# ISO485.net
KiCad netlist of a schematic drawn in EAGLE
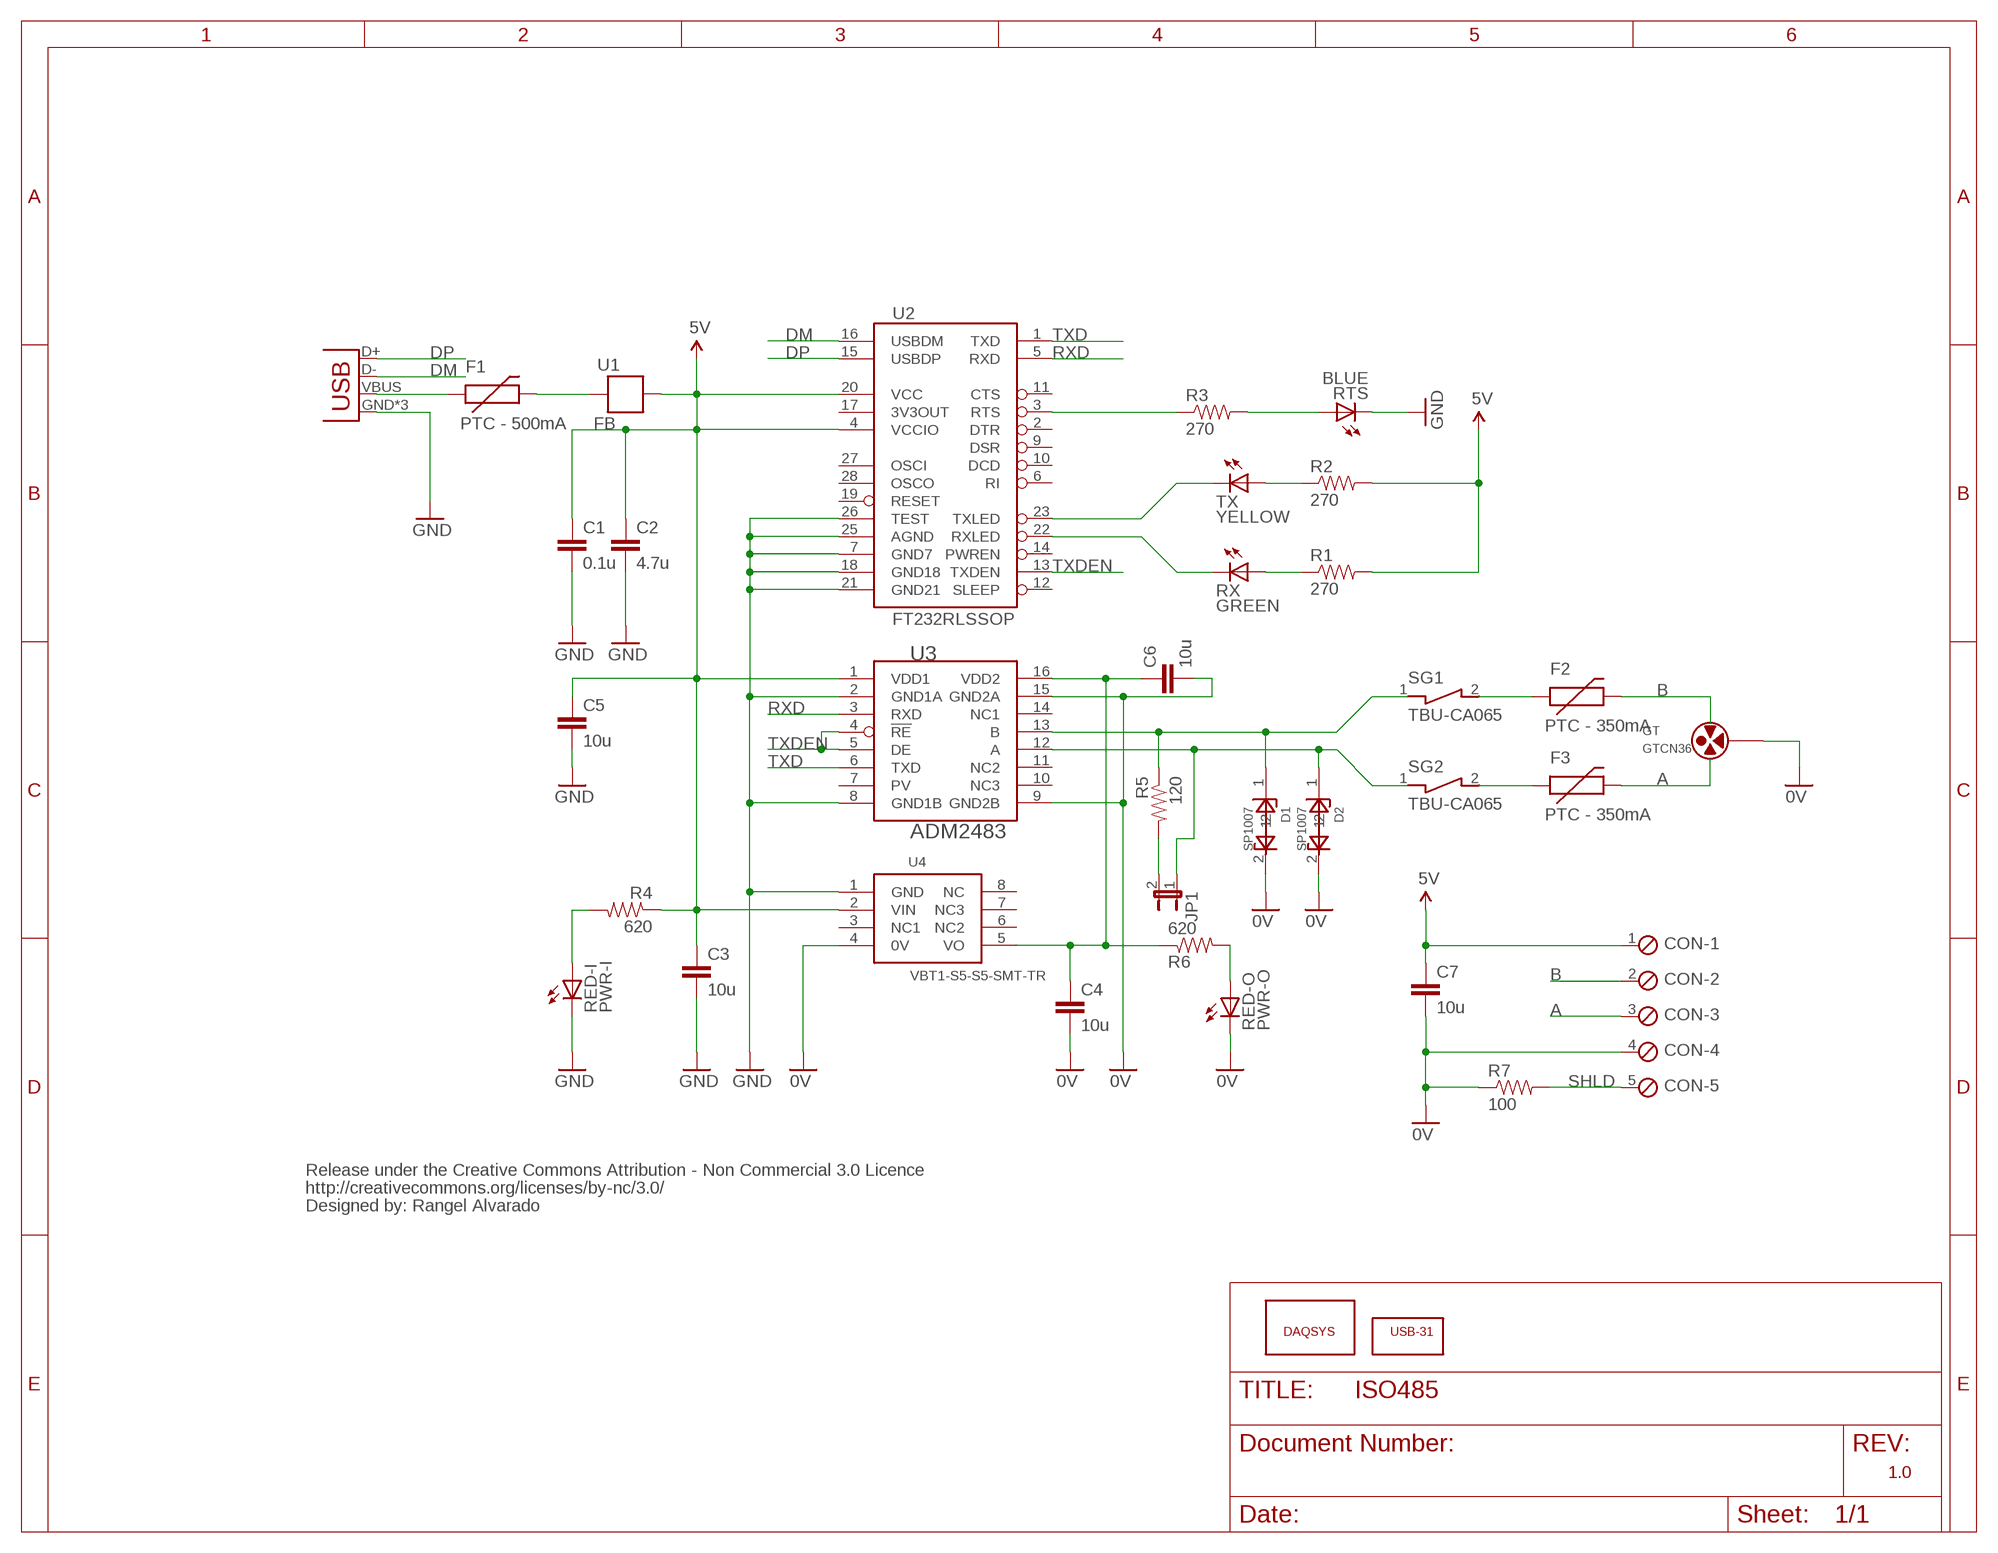
[diagram p0: schematic, sheet 1]

(export (version "E")
  (design (tool "Eeschema 10.0.6"))
  (components
    (comp (ref "C1")
      (value "0.1u")
      (footprint "eagle-import:0603-CAP")
      (libsource (lib "eagle-import") (part "CAP0603-CAP"))
    )
    (comp (ref "C2")
      (value "4.7u")
      (footprint "eagle-import:0603-CAP")
      (libsource (lib "eagle-import") (part "CAP0603-CAP"))
    )
    (comp (ref "C3")
      (value "10u")
      (footprint "eagle-import:0603-CAP")
      (libsource (lib "eagle-import") (part "CAP0603-CAP"))
    )
    (comp (ref "C4")
      (value "10u")
      (footprint "eagle-import:0603-CAP")
      (libsource (lib "eagle-import") (part "CAP0603-CAP"))
    )
    (comp (ref "C5")
      (value "10u")
      (footprint "eagle-import:0603-CAP")
      (libsource (lib "eagle-import") (part "CAP0603-CAP"))
    )
    (comp (ref "C6")
      (value "10u")
      (footprint "eagle-import:0603-CAP")
      (libsource (lib "eagle-import") (part "CAP0603-CAP"))
    )
    (comp (ref "C7")
      (value "10u")
      (footprint "eagle-import:0603-CAP")
      (libsource (lib "eagle-import") (part "CAP0603-CAP"))
    )
    (comp (ref "CON")
      (value "MPT5")
      (footprint "eagle-import:5POL254")
      (libsource (lib "eagle-import") (part "MPT5"))
    )
    (comp (ref "D1")
      (value "SP1007")
      (footprint "eagle-import:0603")
      (libsource (lib "eagle-import") (part "SP1007-01WTG"))
    )
    (comp (ref "D2")
      (value "SP1007")
      (footprint "eagle-import:0603")
      (libsource (lib "eagle-import") (part "SP1007-01WTG"))
    )
    (comp (ref "F1")
      (value "PTC - 500mA")
      (footprint "eagle-import:0603")
      (libsource (lib "eagle-import") (part "PTC0603"))
    )
    (comp (ref "F2")
      (value "PTC - 350mA")
      (footprint "eagle-import:0603")
      (libsource (lib "eagle-import") (part "PTC0603"))
    )
    (comp (ref "F3")
      (value "PTC - 350mA")
      (footprint "eagle-import:0603")
      (libsource (lib "eagle-import") (part "PTC0603"))
    )
    (comp (ref "GT")
      (value "GTCN36")
      (footprint "eagle-import:SMT-GDT")
      (libsource (lib "eagle-import") (part "GTCN36-401M-R05"))
    )
    (comp (ref "JP1")
      (value "JUMPER-2PTH")
      (footprint "eagle-import:1X02")
      (libsource (lib "eagle-import") (part "JUMPER-2PTH"))
    )
    (comp (ref "R1")
      (value "270")
      (footprint "eagle-import:0402-RES")
      (libsource (lib "eagle-import") (part "RESISTOR0402-RES"))
    )
    (comp (ref "R2")
      (value "270")
      (footprint "eagle-import:0402-RES")
      (libsource (lib "eagle-import") (part "RESISTOR0402-RES"))
    )
    (comp (ref "R3")
      (value "270")
      (footprint "eagle-import:0402-RES")
      (libsource (lib "eagle-import") (part "RESISTOR0402-RES"))
    )
    (comp (ref "R4")
      (value "620")
      (footprint "eagle-import:0402-RES")
      (libsource (lib "eagle-import") (part "RESISTOR0402-RES"))
    )
    (comp (ref "R5")
      (value "120")
      (footprint "eagle-import:0402-RES")
      (libsource (lib "eagle-import") (part "RESISTOR0402-RES"))
    )
    (comp (ref "R6")
      (value "620")
      (footprint "eagle-import:0402-RES")
      (libsource (lib "eagle-import") (part "RESISTOR0402-RES"))
    )
    (comp (ref "R7")
      (value "100")
      (footprint "eagle-import:1206")
      (libsource (lib "eagle-import") (part "RESISTOR1206"))
    )
    (comp (ref "RED-I")
      (value "PWR-I")
      (footprint "eagle-import:LED-1206")
      (libsource (lib "eagle-import") (part "LED1206"))
    )
    (comp (ref "RED-O")
      (value "PWR-O")
      (footprint "eagle-import:LED-1206")
      (libsource (lib "eagle-import") (part "LED1206"))
    )
    (comp (ref "RTS")
      (value "BLUE")
      (footprint "eagle-import:LED-0603")
      (libsource (lib "eagle-import") (part "LED0603"))
    )
    (comp (ref "RX")
      (value "GREEN")
      (footprint "eagle-import:LED-0603")
      (libsource (lib "eagle-import") (part "LED-GREEN0603"))
    )
    (comp (ref "SG1")
      (value "TBU-CA065")
      (footprint "eagle-import:SMD")
      (libsource (lib "eagle-import") (part "TBU-CA065-100-WH"))
    )
    (comp (ref "SG2")
      (value "TBU-CA065")
      (footprint "eagle-import:SMD")
      (libsource (lib "eagle-import") (part "TBU-CA065-100-WH"))
    )
    (comp (ref "TX")
      (value "YELLOW")
      (footprint "eagle-import:LED-0603")
      (libsource (lib "eagle-import") (part "LED-YELLOW0603"))
    )
    (comp (ref "U$1")
      (value "CC-BY-NC")
      (footprint "eagle-import:CC-BY-NC")
      (libsource (lib "eagle-import") (part "CC-BY-NC"))
    )
    (comp (ref "U$2")
      (value "DAQSYS")
      (footprint "eagle-import:DAQSYS")
      (libsource (lib "eagle-import") (part "DAQSYS"))
    )
    (comp (ref "U$3")
      (value "USB-31")
      (footprint "eagle-import:USB-PCB-RECT")
      (libsource (lib "eagle-import") (part "USB-31"))
    )
    (comp (ref "U1")
      (value "FB")
      (footprint "eagle-import:0603")
      (libsource (lib "eagle-import") (part "FB"))
    )
    (comp (ref "U2")
      (value "FT232RLSSOP")
      (footprint "eagle-import:SSOP28DB")
      (libsource (lib "eagle-import") (part "FT232RLSSOP"))
    )
    (comp (ref "U3")
      (value "ADM2483")
      (footprint "eagle-import:SOIC-16")
      (libsource (lib "eagle-import") (part "ADM2483"))
    )
    (comp (ref "U4")
      (value "VBT1-S5-S5-SMT-TR")
      (footprint "eagle-import:SMD-8")
      (libsource (lib "eagle-import") (part "VBT1-S5-S5-SMT-TR"))
    )
    (comp (ref "USB")
      (value "USB-MICROB")
      (footprint "eagle-import:USB-MICROB")
      (libsource (lib "eagle-import") (part "USB-MICROB"))
    )
  )
  (nets
    (net (code "1") (name "/A") (class "Default")
      (node (ref "CON") (pin "3") (pinfunction "1_3") (pintype "passive"))
      (node (ref "F3") (pin "2") (pinfunction "2_2") (pintype "bidirectional"))
      (node (ref "GT") (pin "2") (pinfunction "2_2") (pintype "bidirectional"))
    )
    (net (code "2") (name "/B") (class "Default")
      (node (ref "CON") (pin "2") (pinfunction "1_2") (pintype "passive"))
      (node (ref "F2") (pin "2") (pinfunction "2_2") (pintype "bidirectional"))
      (node (ref "GT") (pin "1") (pinfunction "1_1") (pintype "bidirectional"))
    )
    (net (code "3") (name "/DM") (class "Default")
      (node (ref "U2") (pin "16") (pinfunction "USBDM_16") (pintype "bidirectional"))
      (node (ref "USB") (pin "D-") (pinfunction "D-_D-") (pintype "bidirectional"))
    )
    (net (code "4") (name "/DP") (class "Default")
      (node (ref "U2") (pin "15") (pinfunction "USBDP_15") (pintype "bidirectional"))
      (node (ref "USB") (pin "D+") (pinfunction "D+_D+") (pintype "bidirectional"))
    )
    (net (code "5") (name "/RXD") (class "Default")
      (node (ref "U2") (pin "5") (pinfunction "RXD_5") (pintype "input"))
      (node (ref "U3") (pin "3") (pinfunction "RXD_3") (pintype "bidirectional"))
    )
    (net (code "6") (name "/SHLD") (class "Default")
      (node (ref "CON") (pin "5") (pinfunction "1_5") (pintype "passive"))
      (node (ref "R7") (pin "2") (pinfunction "2_2") (pintype "passive"))
    )
    (net (code "7") (name "/TXD") (class "Default")
      (node (ref "U2") (pin "1") (pinfunction "TXD_1") (pintype "output"))
      (node (ref "U3") (pin "6") (pinfunction "TXD_6") (pintype "bidirectional"))
    )
    (net (code "8") (name "/TXDEN") (class "Default")
      (node (ref "U2") (pin "13") (pinfunction "TXDEN_13") (pintype "input"))
      (node (ref "U3") (pin "4") (pinfunction "~{RE}_4") (pintype "bidirectional"))
      (node (ref "U3") (pin "5") (pinfunction "DE_5") (pintype "bidirectional"))
    )
    (net (code "9") (name "0V") (class "Default")
      (node (ref "C4") (pin "2") (pinfunction "2_2") (pintype "passive"))
      (node (ref "C6") (pin "2") (pinfunction "2_2") (pintype "passive"))
      (node (ref "C7") (pin "2") (pinfunction "2_2") (pintype "passive"))
      (node (ref "CON") (pin "4") (pinfunction "1_4") (pintype "passive"))
      (node (ref "D1") (pin "2") (pinfunction "2_2") (pintype "bidirectional"))
      (node (ref "D2") (pin "2") (pinfunction "2_2") (pintype "bidirectional"))
      (node (ref "GT") (pin "3") (pinfunction "3_3") (pintype "bidirectional"))
      (node (ref "R7") (pin "1") (pinfunction "1_1") (pintype "passive"))
      (node (ref "RED-O") (pin "C") (pinfunction "C_C") (pintype "passive"))
      (node (ref "U3") (pin "15") (pinfunction "GND2A_15") (pintype "bidirectional"))
      (node (ref "U3") (pin "9") (pinfunction "GND2B_9") (pintype "bidirectional"))
      (node (ref "U4") (pin "4") (pinfunction "0V_4") (pintype "bidirectional"))
    )
    (net (code "10") (name "5V") (class "Default")
      (node (ref "C1") (pin "1") (pinfunction "1_1") (pintype "passive"))
      (node (ref "C2") (pin "1") (pinfunction "1_1") (pintype "passive"))
      (node (ref "C3") (pin "1") (pinfunction "1_1") (pintype "passive"))
      (node (ref "C5") (pin "1") (pinfunction "1_1") (pintype "passive"))
      (node (ref "C7") (pin "1") (pinfunction "1_1") (pintype "passive"))
      (node (ref "CON") (pin "1") (pinfunction "1_1") (pintype "passive"))
      (node (ref "R1") (pin "2") (pinfunction "2_2") (pintype "passive"))
      (node (ref "R2") (pin "2") (pinfunction "2_2") (pintype "passive"))
      (node (ref "R4") (pin "1") (pinfunction "1_1") (pintype "passive"))
      (node (ref "U1") (pin "1") (pinfunction "P$1_1") (pintype "bidirectional"))
      (node (ref "U2") (pin "20") (pinfunction "VCC_20") (pintype "power_in"))
      (node (ref "U2") (pin "4") (pinfunction "VCCIO_4") (pintype "power_in"))
      (node (ref "U3") (pin "1") (pinfunction "VDD1_1") (pintype "bidirectional"))
      (node (ref "U4") (pin "2") (pinfunction "VIN_2") (pintype "bidirectional"))
    )
    (net (code "11") (name "GND") (class "Default")
      (node (ref "C1") (pin "2") (pinfunction "2_2") (pintype "passive"))
      (node (ref "C2") (pin "2") (pinfunction "2_2") (pintype "passive"))
      (node (ref "C3") (pin "2") (pinfunction "2_2") (pintype "passive"))
      (node (ref "C5") (pin "2") (pinfunction "2_2") (pintype "passive"))
      (node (ref "RED-I") (pin "C") (pinfunction "C_C") (pintype "passive"))
      (node (ref "RTS") (pin "C") (pinfunction "C_C") (pintype "passive"))
      (node (ref "U2") (pin "18") (pinfunction "GND18_18") (pintype "power_in"))
      (node (ref "U2") (pin "21") (pinfunction "GND21_21") (pintype "power_in"))
      (node (ref "U2") (pin "25") (pinfunction "AGND_25") (pintype "power_in"))
      (node (ref "U2") (pin "26") (pinfunction "TEST_26") (pintype "input"))
      (node (ref "U2") (pin "7") (pinfunction "GND7_7") (pintype "power_in"))
      (node (ref "U3") (pin "2") (pinfunction "GND1A_2") (pintype "bidirectional"))
      (node (ref "U3") (pin "8") (pinfunction "GND1B_8") (pintype "bidirectional"))
      (node (ref "U4") (pin "1") (pinfunction "GND_1") (pintype "bidirectional"))
      (node (ref "USB") (pin "GND") (pinfunction "GND_GND") (pintype "bidirectional"))
      (node (ref "USB") (pin "MT1") (pinfunction "GND_MT1") (pintype "bidirectional"))
      (node (ref "USB") (pin "MT2") (pinfunction "GND_MT2") (pintype "bidirectional"))
    )
    (net (code "12") (name "Net-(F1-Pad1)") (class "Default")
      (node (ref "F1") (pin "1") (pinfunction "1_1") (pintype "bidirectional"))
      (node (ref "USB") (pin "VBUS") (pinfunction "VBUS_VBUS") (pintype "bidirectional"))
    )
    (net (code "13") (name "Net-(JP1-Pad2)") (class "Default")
      (node (ref "JP1") (pin "2") (pinfunction "2_2") (pintype "passive"))
      (node (ref "R5") (pin "2") (pinfunction "2_2") (pintype "passive"))
    )
    (net (code "14") (name "Net-(R1-Pad1)") (class "Default")
      (node (ref "R1") (pin "1") (pinfunction "1_1") (pintype "passive"))
      (node (ref "RX") (pin "A") (pinfunction "A_A") (pintype "passive"))
    )
    (net (code "15") (name "Net-(R2-Pad1)") (class "Default")
      (node (ref "R2") (pin "1") (pinfunction "1_1") (pintype "passive"))
      (node (ref "TX") (pin "A") (pinfunction "A_A") (pintype "passive"))
    )
    (net (code "16") (name "Net-(R3-Pad2)") (class "Default")
      (node (ref "R3") (pin "2") (pinfunction "2_2") (pintype "passive"))
      (node (ref "RTS") (pin "A") (pinfunction "A_A") (pintype "passive"))
    )
    (net (code "17") (name "Net-(R4-Pad2)") (class "Default")
      (node (ref "R4") (pin "2") (pinfunction "2_2") (pintype "passive"))
      (node (ref "RED-I") (pin "A") (pinfunction "A_A") (pintype "passive"))
    )
    (net (code "18") (name "Net-(R6-Pad2)") (class "Default")
      (node (ref "R6") (pin "2") (pinfunction "2_2") (pintype "passive"))
      (node (ref "RED-O") (pin "A") (pinfunction "A_A") (pintype "passive"))
    )
    (net (code "19") (name "Net-(SG1-P$1)") (class "Default")
      (node (ref "D1") (pin "1") (pinfunction "1_1") (pintype "bidirectional"))
      (node (ref "R5") (pin "1") (pinfunction "1_1") (pintype "passive"))
      (node (ref "SG1") (pin "1") (pinfunction "P$1_1") (pintype "bidirectional"))
      (node (ref "U3") (pin "13") (pinfunction "B_13") (pintype "bidirectional"))
    )
    (net (code "20") (name "Net-(SG1-P$2)") (class "Default")
      (node (ref "F2") (pin "1") (pinfunction "1_1") (pintype "bidirectional"))
      (node (ref "SG1") (pin "2") (pinfunction "P$2_2") (pintype "bidirectional"))
    )
    (net (code "21") (name "Net-(SG2-P$1)") (class "Default")
      (node (ref "D2") (pin "1") (pinfunction "1_1") (pintype "bidirectional"))
      (node (ref "JP1") (pin "1") (pinfunction "1_1") (pintype "passive"))
      (node (ref "SG2") (pin "1") (pinfunction "P$1_1") (pintype "bidirectional"))
      (node (ref "U3") (pin "12") (pinfunction "A_12") (pintype "bidirectional"))
    )
    (net (code "22") (name "Net-(SG2-P$2)") (class "Default")
      (node (ref "F3") (pin "1") (pinfunction "1_1") (pintype "bidirectional"))
      (node (ref "SG2") (pin "2") (pinfunction "P$2_2") (pintype "bidirectional"))
    )
    (net (code "23") (name "Net-(U1-P$2)") (class "Default")
      (node (ref "F1") (pin "2") (pinfunction "2_2") (pintype "bidirectional"))
      (node (ref "U1") (pin "2") (pinfunction "P$2_2") (pintype "bidirectional"))
    )
    (net (code "24") (name "Net-(U2-RTS)") (class "Default")
      (node (ref "R3") (pin "1") (pinfunction "1_1") (pintype "passive"))
      (node (ref "U2") (pin "3") (pinfunction "RTS_3") (pintype "output"))
    )
    (net (code "25") (name "Net-(U2-RXLED)") (class "Default")
      (node (ref "RX") (pin "C") (pinfunction "C_C") (pintype "passive"))
      (node (ref "U2") (pin "22") (pinfunction "RXLED_22") (pintype "input"))
    )
    (net (code "26") (name "Net-(U2-TXLED)") (class "Default")
      (node (ref "TX") (pin "C") (pinfunction "C_C") (pintype "passive"))
      (node (ref "U2") (pin "23") (pinfunction "TXLED_23") (pintype "input"))
    )
    (net (code "27") (name "Net-(U3-VDD2)") (class "Default")
      (node (ref "C4") (pin "1") (pinfunction "1_1") (pintype "passive"))
      (node (ref "C6") (pin "1") (pinfunction "1_1") (pintype "passive"))
      (node (ref "R6") (pin "1") (pinfunction "1_1") (pintype "passive"))
      (node (ref "U3") (pin "16") (pinfunction "VDD2_16") (pintype "bidirectional"))
      (node (ref "U4") (pin "5") (pinfunction "VO_5") (pintype "bidirectional"))
    )
    (net (code "28") (name "unconnected-(U2-3V3OUT-Pad17)") (class "Default")
      (node (ref "U2") (pin "17") (pinfunction "3V3OUT_17") (pintype "output"))
    )
    (net (code "29") (name "unconnected-(U2-CTS-Pad11)") (class "Default")
      (node (ref "U2") (pin "11") (pinfunction "CTS_11") (pintype "input"))
    )
    (net (code "30") (name "unconnected-(U2-DCD-Pad10)") (class "Default")
      (node (ref "U2") (pin "10") (pinfunction "DCD_10") (pintype "input"))
    )
    (net (code "31") (name "unconnected-(U2-DSR-Pad9)") (class "Default")
      (node (ref "U2") (pin "9") (pinfunction "DSR_9") (pintype "input"))
    )
    (net (code "32") (name "unconnected-(U2-DTR-Pad2)") (class "Default")
      (node (ref "U2") (pin "2") (pinfunction "DTR_2") (pintype "output"))
    )
    (net (code "33") (name "unconnected-(U2-OSCI-Pad27)") (class "Default")
      (node (ref "U2") (pin "27") (pinfunction "OSCI_27") (pintype "input"))
    )
    (net (code "34") (name "unconnected-(U2-OSCO-Pad28)") (class "Default")
      (node (ref "U2") (pin "28") (pinfunction "OSCO_28") (pintype "output"))
    )
    (net (code "35") (name "unconnected-(U2-PWREN-Pad14)") (class "Default")
      (node (ref "U2") (pin "14") (pinfunction "PWREN_14") (pintype "input"))
    )
    (net (code "36") (name "unconnected-(U2-RESET-Pad19)") (class "Default")
      (node (ref "U2") (pin "19") (pinfunction "RESET_19") (pintype "input"))
    )
    (net (code "37") (name "unconnected-(U2-RI-Pad6)") (class "Default")
      (node (ref "U2") (pin "6") (pinfunction "RI_6") (pintype "input"))
    )
    (net (code "38") (name "unconnected-(U2-SLEEP-Pad12)") (class "Default")
      (node (ref "U2") (pin "12") (pinfunction "SLEEP_12") (pintype "input"))
    )
    (net (code "39") (name "unconnected-(U3-NC1-Pad14)") (class "Default")
      (node (ref "U3") (pin "14") (pinfunction "NC1_14") (pintype "bidirectional"))
    )
    (net (code "40") (name "unconnected-(U3-NC2-Pad11)") (class "Default")
      (node (ref "U3") (pin "11") (pinfunction "NC2_11") (pintype "bidirectional"))
    )
    (net (code "41") (name "unconnected-(U3-NC3-Pad10)") (class "Default")
      (node (ref "U3") (pin "10") (pinfunction "NC3_10") (pintype "bidirectional"))
    )
    (net (code "42") (name "unconnected-(U3-PV-Pad7)") (class "Default")
      (node (ref "U3") (pin "7") (pinfunction "PV_7") (pintype "bidirectional"))
    )
    (net (code "43") (name "unconnected-(U4-NC-Pad8)") (class "Default")
      (node (ref "U4") (pin "8") (pinfunction "NC_8") (pintype "bidirectional"))
    )
    (net (code "44") (name "unconnected-(U4-NC1-Pad3)") (class "Default")
      (node (ref "U4") (pin "3") (pinfunction "NC1_3") (pintype "bidirectional"))
    )
    (net (code "45") (name "unconnected-(U4-NC2-Pad6)") (class "Default")
      (node (ref "U4") (pin "6") (pinfunction "NC2_6") (pintype "bidirectional"))
    )
    (net (code "46") (name "unconnected-(U4-NC3-Pad7)") (class "Default")
      (node (ref "U4") (pin "7") (pinfunction "NC3_7") (pintype "bidirectional"))
    )
  )
)
